# RotaryEncoder_Breakout_3ch.net
KiCad netlist of a schematic drawn in EAGLE
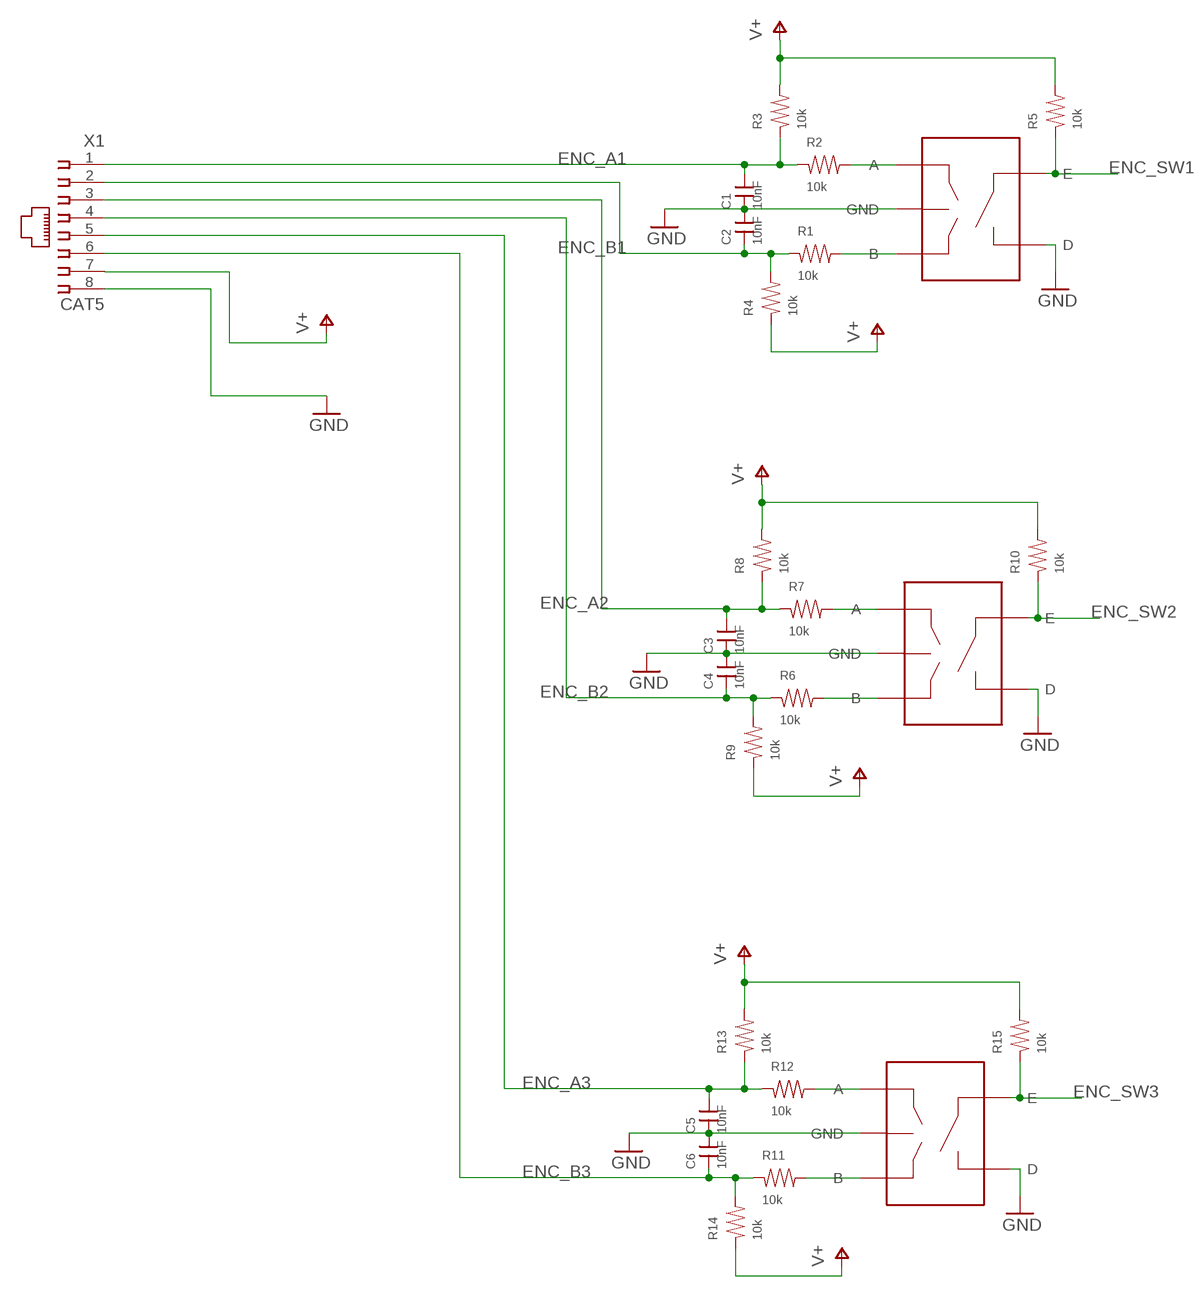
[diagram p0: schematic, sheet 1]

(export (version "E")
  (design (tool "Eeschema 10.0.6"))
  (components
    (comp (ref "C1")
      (value "10nF")
      (footprint "eagle-import:0603")
      (libsource (lib "eagle-import") (part "CAP0603"))
    )
    (comp (ref "C2")
      (value "10nF")
      (footprint "eagle-import:0603")
      (libsource (lib "eagle-import") (part "CAP0603"))
    )
    (comp (ref "C3")
      (value "10nF")
      (footprint "eagle-import:0603")
      (libsource (lib "eagle-import") (part "CAP0603"))
    )
    (comp (ref "C4")
      (value "10nF")
      (footprint "eagle-import:0603")
      (libsource (lib "eagle-import") (part "CAP0603"))
    )
    (comp (ref "C5")
      (value "10nF")
      (footprint "eagle-import:0603")
      (libsource (lib "eagle-import") (part "CAP0603"))
    )
    (comp (ref "C6")
      (value "10nF")
      (footprint "eagle-import:0603")
      (libsource (lib "eagle-import") (part "CAP0603"))
    )
    (comp (ref "ENC1")
      (value "PEC09")
      (footprint "eagle-import:PEC092320FS")
      (libsource (lib "eagle-import") (part "PEC09"))
    )
    (comp (ref "ENC2")
      (value "PEC09")
      (footprint "eagle-import:PEC092320FS")
      (libsource (lib "eagle-import") (part "PEC09"))
    )
    (comp (ref "ENC3")
      (value "PEC09")
      (footprint "eagle-import:PEC092320FS")
      (libsource (lib "eagle-import") (part "PEC09"))
    )
    (comp (ref "R1")
      (value "10k")
      (footprint "eagle-import:0603")
      (libsource (lib "eagle-import") (part "RES0603"))
    )
    (comp (ref "R2")
      (value "10k")
      (footprint "eagle-import:0603")
      (libsource (lib "eagle-import") (part "RES0603"))
    )
    (comp (ref "R3")
      (value "10k")
      (footprint "eagle-import:0603")
      (libsource (lib "eagle-import") (part "RES0603"))
    )
    (comp (ref "R4")
      (value "10k")
      (footprint "eagle-import:0603")
      (libsource (lib "eagle-import") (part "RES0603"))
    )
    (comp (ref "R5")
      (value "10k")
      (footprint "eagle-import:0603")
      (libsource (lib "eagle-import") (part "RES0603"))
    )
    (comp (ref "R6")
      (value "10k")
      (footprint "eagle-import:0603")
      (libsource (lib "eagle-import") (part "RES0603"))
    )
    (comp (ref "R7")
      (value "10k")
      (footprint "eagle-import:0603")
      (libsource (lib "eagle-import") (part "RES0603"))
    )
    (comp (ref "R8")
      (value "10k")
      (footprint "eagle-import:0603")
      (libsource (lib "eagle-import") (part "RES0603"))
    )
    (comp (ref "R9")
      (value "10k")
      (footprint "eagle-import:0603")
      (libsource (lib "eagle-import") (part "RES0603"))
    )
    (comp (ref "R10")
      (value "10k")
      (footprint "eagle-import:0603")
      (libsource (lib "eagle-import") (part "RES0603"))
    )
    (comp (ref "R11")
      (value "10k")
      (footprint "eagle-import:0603")
      (libsource (lib "eagle-import") (part "RES0603"))
    )
    (comp (ref "R12")
      (value "10k")
      (footprint "eagle-import:0603")
      (libsource (lib "eagle-import") (part "RES0603"))
    )
    (comp (ref "R13")
      (value "10k")
      (footprint "eagle-import:0603")
      (libsource (lib "eagle-import") (part "RES0603"))
    )
    (comp (ref "R14")
      (value "10k")
      (footprint "eagle-import:0603")
      (libsource (lib "eagle-import") (part "RES0603"))
    )
    (comp (ref "R15")
      (value "10k")
      (footprint "eagle-import:0603")
      (libsource (lib "eagle-import") (part "RES0603"))
    )
    (comp (ref "X1")
      (value "CAT5")
      (footprint "eagle-import:555164-1")
      (libsource (lib "eagle-import") (part "CAT5"))
    )
  )
  (nets
    (net (code "1") (name "/ENC_A1") (class "Default")
      (node (ref "C1") (pin "2") (pinfunction "P$2_2") (pintype "passive"))
      (node (ref "R2") (pin "1") (pinfunction "P$1_1") (pintype "passive"))
      (node (ref "R3") (pin "1") (pinfunction "P$1_1") (pintype "passive"))
      (node (ref "X1") (pin "1") (pinfunction "1_1") (pintype "passive"))
    )
    (net (code "2") (name "/ENC_A2") (class "Default")
      (node (ref "C3") (pin "2") (pinfunction "P$2_2") (pintype "passive"))
      (node (ref "R7") (pin "1") (pinfunction "P$1_1") (pintype "passive"))
      (node (ref "R8") (pin "1") (pinfunction "P$1_1") (pintype "passive"))
      (node (ref "X1") (pin "3") (pinfunction "3_3") (pintype "passive"))
    )
    (net (code "3") (name "/ENC_A3") (class "Default")
      (node (ref "C5") (pin "2") (pinfunction "P$2_2") (pintype "passive"))
      (node (ref "R12") (pin "1") (pinfunction "P$1_1") (pintype "passive"))
      (node (ref "R13") (pin "1") (pinfunction "P$1_1") (pintype "passive"))
      (node (ref "X1") (pin "5") (pinfunction "5_5") (pintype "passive"))
    )
    (net (code "4") (name "/ENC_B1") (class "Default")
      (node (ref "C2") (pin "1") (pinfunction "P$1_1") (pintype "passive"))
      (node (ref "R1") (pin "1") (pinfunction "P$1_1") (pintype "passive"))
      (node (ref "R4") (pin "2") (pinfunction "P$2_2") (pintype "passive"))
      (node (ref "X1") (pin "2") (pinfunction "2_2") (pintype "passive"))
    )
    (net (code "5") (name "/ENC_B2") (class "Default")
      (node (ref "C4") (pin "1") (pinfunction "P$1_1") (pintype "passive"))
      (node (ref "R6") (pin "1") (pinfunction "P$1_1") (pintype "passive"))
      (node (ref "R9") (pin "2") (pinfunction "P$2_2") (pintype "passive"))
      (node (ref "X1") (pin "4") (pinfunction "4_4") (pintype "passive"))
    )
    (net (code "6") (name "/ENC_B3") (class "Default")
      (node (ref "C6") (pin "1") (pinfunction "P$1_1") (pintype "passive"))
      (node (ref "R11") (pin "1") (pinfunction "P$1_1") (pintype "passive"))
      (node (ref "R14") (pin "2") (pinfunction "P$2_2") (pintype "passive"))
      (node (ref "X1") (pin "6") (pinfunction "6_6") (pintype "passive"))
    )
    (net (code "7") (name "/ENC_SW1") (class "Default")
      (node (ref "ENC1") (pin "E") (pinfunction "E_E") (pintype "bidirectional"))
      (node (ref "R5") (pin "1") (pinfunction "P$1_1") (pintype "passive"))
    )
    (net (code "8") (name "/ENC_SW2") (class "Default")
      (node (ref "ENC2") (pin "E") (pinfunction "E_E") (pintype "bidirectional"))
      (node (ref "R10") (pin "1") (pinfunction "P$1_1") (pintype "passive"))
    )
    (net (code "9") (name "/ENC_SW3") (class "Default")
      (node (ref "ENC3") (pin "E") (pinfunction "E_E") (pintype "bidirectional"))
      (node (ref "R15") (pin "1") (pinfunction "P$1_1") (pintype "passive"))
    )
    (net (code "10") (name "GND") (class "Default")
      (node (ref "C1") (pin "1") (pinfunction "P$1_1") (pintype "passive"))
      (node (ref "C2") (pin "2") (pinfunction "P$2_2") (pintype "passive"))
      (node (ref "C3") (pin "1") (pinfunction "P$1_1") (pintype "passive"))
      (node (ref "C4") (pin "2") (pinfunction "P$2_2") (pintype "passive"))
      (node (ref "C5") (pin "1") (pinfunction "P$1_1") (pintype "passive"))
      (node (ref "C6") (pin "2") (pinfunction "P$2_2") (pintype "passive"))
      (node (ref "ENC1") (pin "C") (pinfunction "GND_C") (pintype "bidirectional"))
      (node (ref "ENC1") (pin "D") (pinfunction "D_D") (pintype "bidirectional"))
      (node (ref "ENC2") (pin "C") (pinfunction "GND_C") (pintype "bidirectional"))
      (node (ref "ENC2") (pin "D") (pinfunction "D_D") (pintype "bidirectional"))
      (node (ref "ENC3") (pin "C") (pinfunction "GND_C") (pintype "bidirectional"))
      (node (ref "ENC3") (pin "D") (pinfunction "D_D") (pintype "bidirectional"))
      (node (ref "X1") (pin "8") (pinfunction "8_8") (pintype "passive"))
    )
    (net (code "11") (name "Net-(R1-P$2)") (class "Default")
      (node (ref "ENC1") (pin "B") (pinfunction "B_B") (pintype "bidirectional"))
      (node (ref "R1") (pin "2") (pinfunction "P$2_2") (pintype "passive"))
    )
    (net (code "12") (name "Net-(R2-P$2)") (class "Default")
      (node (ref "ENC1") (pin "A") (pinfunction "A_A") (pintype "bidirectional"))
      (node (ref "R2") (pin "2") (pinfunction "P$2_2") (pintype "passive"))
    )
    (net (code "13") (name "Net-(R6-P$2)") (class "Default")
      (node (ref "ENC2") (pin "B") (pinfunction "B_B") (pintype "bidirectional"))
      (node (ref "R6") (pin "2") (pinfunction "P$2_2") (pintype "passive"))
    )
    (net (code "14") (name "Net-(R7-P$2)") (class "Default")
      (node (ref "ENC2") (pin "A") (pinfunction "A_A") (pintype "bidirectional"))
      (node (ref "R7") (pin "2") (pinfunction "P$2_2") (pintype "passive"))
    )
    (net (code "15") (name "Net-(R11-P$2)") (class "Default")
      (node (ref "ENC3") (pin "B") (pinfunction "B_B") (pintype "bidirectional"))
      (node (ref "R11") (pin "2") (pinfunction "P$2_2") (pintype "passive"))
    )
    (net (code "16") (name "Net-(R12-P$2)") (class "Default")
      (node (ref "ENC3") (pin "A") (pinfunction "A_A") (pintype "bidirectional"))
      (node (ref "R12") (pin "2") (pinfunction "P$2_2") (pintype "passive"))
    )
    (net (code "17") (name "V+") (class "Default")
      (node (ref "R10") (pin "2") (pinfunction "P$2_2") (pintype "passive"))
      (node (ref "R13") (pin "2") (pinfunction "P$2_2") (pintype "passive"))
      (node (ref "R14") (pin "1") (pinfunction "P$1_1") (pintype "passive"))
      (node (ref "R15") (pin "2") (pinfunction "P$2_2") (pintype "passive"))
      (node (ref "R3") (pin "2") (pinfunction "P$2_2") (pintype "passive"))
      (node (ref "R4") (pin "1") (pinfunction "P$1_1") (pintype "passive"))
      (node (ref "R5") (pin "2") (pinfunction "P$2_2") (pintype "passive"))
      (node (ref "R8") (pin "2") (pinfunction "P$2_2") (pintype "passive"))
      (node (ref "R9") (pin "1") (pinfunction "P$1_1") (pintype "passive"))
      (node (ref "X1") (pin "7") (pinfunction "7_7") (pintype "passive"))
    )
  )
)
